# Sp_pico.net
KiCad netlist of a schematic drawn in EAGLE
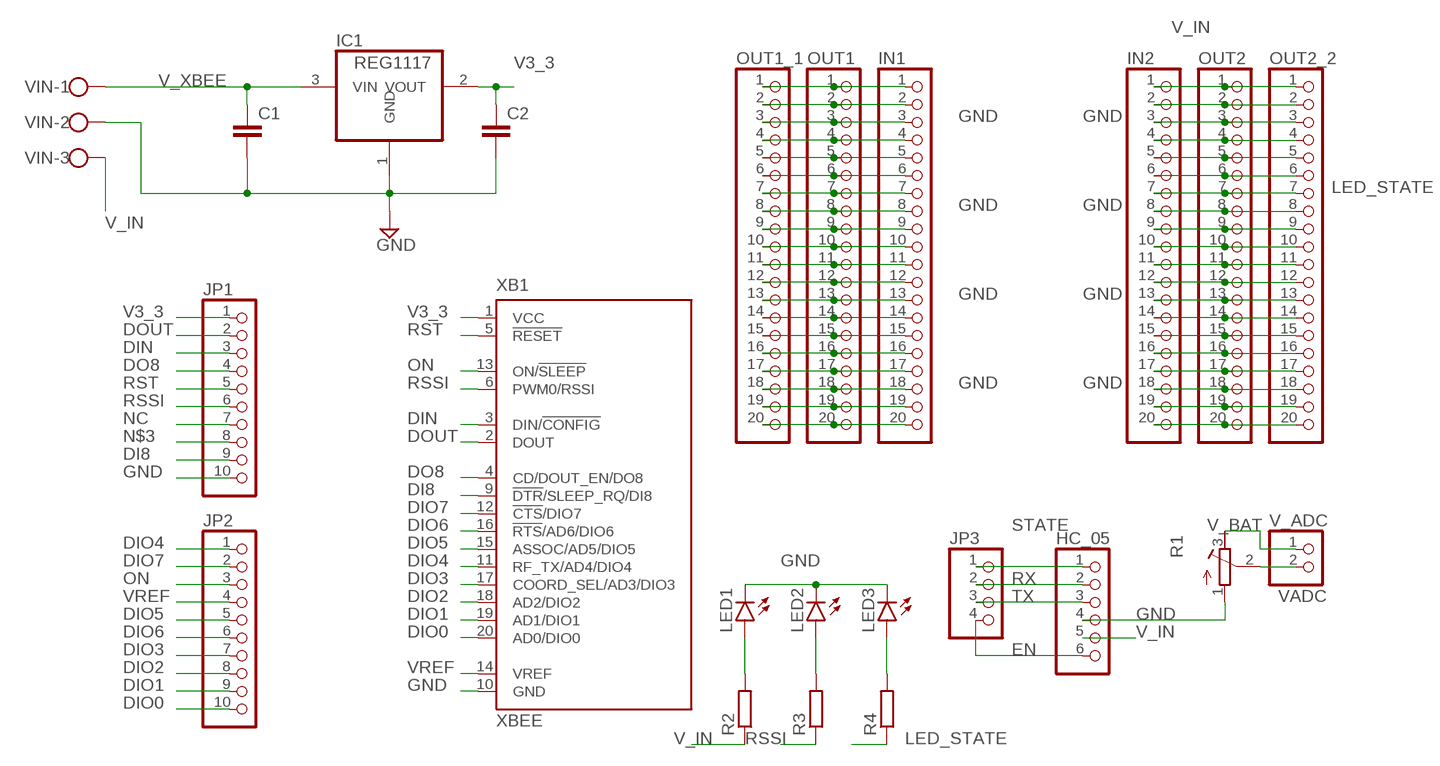
[diagram p0: schematic, sheet 1]

(export (version "E")
  (design (tool "Eeschema 10.0.6"))
  (components
    (comp (ref "C1")
      (value "C2.5/5")
      (footprint "eagle-import:C2.5-5")
      (libsource (lib "eagle-import") (part "C2.5/5"))
    )
    (comp (ref "C2")
      (value "C2.5/5")
      (footprint "eagle-import:C2.5-5")
      (libsource (lib "eagle-import") (part "C2.5/5"))
    )
    (comp (ref "HC_05")
      (value "PINHD-1X6")
      (footprint "eagle-import:1X06")
      (libsource (lib "eagle-import") (part "PINHD-1X6"))
    )
    (comp (ref "IC1")
      (value "REG1117")
      (footprint "eagle-import:SOT223")
      (libsource (lib "eagle-import") (part "REG1117"))
    )
    (comp (ref "IN1")
      (value "PINHD-1X20")
      (footprint "eagle-import:1X20")
      (libsource (lib "eagle-import") (part "PINHD-1X20"))
    )
    (comp (ref "IN2")
      (value "PINHD-1X20")
      (footprint "eagle-import:1X20")
      (libsource (lib "eagle-import") (part "PINHD-1X20"))
    )
    (comp (ref "JP1")
      (value "PINHD-1X10")
      (footprint "eagle-import:1X10")
      (libsource (lib "eagle-import") (part "PINHD-1X10"))
    )
    (comp (ref "JP2")
      (value "PINHD-1X10")
      (footprint "eagle-import:1X10")
      (libsource (lib "eagle-import") (part "PINHD-1X10"))
    )
    (comp (ref "JP3")
      (value "PINHD-1X4")
      (footprint "eagle-import:1X04")
      (libsource (lib "eagle-import") (part "PINHD-1X4"))
    )
    (comp (ref "LED1")
      (value "LED5MM")
      (footprint "eagle-import:LED5MM")
      (libsource (lib "eagle-import") (part "LED5MM"))
    )
    (comp (ref "LED2")
      (value "LED5MM")
      (footprint "eagle-import:LED5MM")
      (libsource (lib "eagle-import") (part "LED5MM"))
    )
    (comp (ref "LED3")
      (value "LED5MM")
      (footprint "eagle-import:LED5MM")
      (libsource (lib "eagle-import") (part "LED5MM"))
    )
    (comp (ref "OUT1")
      (value "PINHD-1X20")
      (footprint "eagle-import:1X20")
      (libsource (lib "eagle-import") (part "PINHD-1X20"))
    )
    (comp (ref "OUT1_1")
      (value "PINHD-1X20")
      (footprint "eagle-import:1X20")
      (libsource (lib "eagle-import") (part "PINHD-1X20"))
    )
    (comp (ref "OUT2")
      (value "PINHD-1X20")
      (footprint "eagle-import:1X20")
      (libsource (lib "eagle-import") (part "PINHD-1X20"))
    )
    (comp (ref "OUT2_2")
      (value "PINHD-1X20")
      (footprint "eagle-import:1X20")
      (libsource (lib "eagle-import") (part "PINHD-1X20"))
    )
    (comp (ref "R1")
      (value "R-TRIMM3296X")
      (footprint "eagle-import:RTRIM3296X")
      (libsource (lib "eagle-import") (part "R-TRIMM3296X"))
    )
    (comp (ref "R2")
      (value "R-EU_0204/7")
      (footprint "eagle-import:0204_7")
      (libsource (lib "eagle-import") (part "R-EU_0204/7"))
    )
    (comp (ref "R3")
      (value "R-EU_0204/7")
      (footprint "eagle-import:0204_7")
      (libsource (lib "eagle-import") (part "R-EU_0204/7"))
    )
    (comp (ref "R4")
      (value "R-EU_0204/7")
      (footprint "eagle-import:0204_7")
      (libsource (lib "eagle-import") (part "R-EU_0204/7"))
    )
    (comp (ref "VIN")
      (value "W237-103")
      (footprint "eagle-import:W237-103")
      (fields (field (name "MPN") "237-103"))
      (libsource (lib "eagle-import") (part "W237-103"))
    )
    (comp (ref "V_ADC")
      (value "PINHD-1X2")
      (footprint "eagle-import:1X02")
      (libsource (lib "eagle-import") (part "PINHD-1X2"))
    )
    (comp (ref "XB1")
      (value "XBEE")
      (footprint "eagle-import:XBEE")
      (fields (field (name "MPN") "XBP24-Z7UIT-004"))
      (libsource (lib "eagle-import") (part "XBEE"))
    )
  )
  (nets
    (net (code "1") (name "/DI8") (class "Default")
      (node (ref "JP1") (pin "9") (pinfunction "9_9") (pintype "passive"))
      (node (ref "XB1") (pin "9") (pinfunction "~{DTR}/SLEEP_RQ/DI8_9") (pintype "bidirectional"))
    )
    (net (code "2") (name "/DIN") (class "Default")
      (node (ref "JP1") (pin "3") (pinfunction "3_3") (pintype "passive"))
      (node (ref "XB1") (pin "3") (pinfunction "DIN/~{CONFIG}_3") (pintype "input"))
    )
    (net (code "3") (name "/DIO0") (class "Default")
      (node (ref "JP2") (pin "10") (pinfunction "10_10") (pintype "passive"))
      (node (ref "XB1") (pin "20") (pinfunction "AD0/DIO0_20") (pintype "bidirectional"))
    )
    (net (code "4") (name "/DIO1") (class "Default")
      (node (ref "JP2") (pin "9") (pinfunction "9_9") (pintype "passive"))
      (node (ref "XB1") (pin "19") (pinfunction "AD1/DIO1_19") (pintype "bidirectional"))
    )
    (net (code "5") (name "/DIO2") (class "Default")
      (node (ref "JP2") (pin "8") (pinfunction "8_8") (pintype "passive"))
      (node (ref "XB1") (pin "18") (pinfunction "AD2/DIO2_18") (pintype "bidirectional"))
    )
    (net (code "6") (name "/DIO3") (class "Default")
      (node (ref "JP2") (pin "7") (pinfunction "7_7") (pintype "passive"))
      (node (ref "XB1") (pin "17") (pinfunction "COORD_SEL/AD3/DIO3_17") (pintype "bidirectional"))
    )
    (net (code "7") (name "/DIO4") (class "Default")
      (node (ref "JP2") (pin "1") (pinfunction "1_1") (pintype "passive"))
      (node (ref "XB1") (pin "11") (pinfunction "RF_TX/AD4/DIO4_11") (pintype "bidirectional"))
    )
    (net (code "8") (name "/DIO5") (class "Default")
      (node (ref "JP2") (pin "5") (pinfunction "5_5") (pintype "passive"))
      (node (ref "XB1") (pin "15") (pinfunction "ASSOC/AD5/DIO5_15") (pintype "bidirectional"))
    )
    (net (code "9") (name "/DIO6") (class "Default")
      (node (ref "JP2") (pin "6") (pinfunction "6_6") (pintype "passive"))
      (node (ref "XB1") (pin "16") (pinfunction "~{RTS}/AD6/DIO6_16") (pintype "bidirectional"))
    )
    (net (code "10") (name "/DIO7") (class "Default")
      (node (ref "JP2") (pin "2") (pinfunction "2_2") (pintype "passive"))
      (node (ref "XB1") (pin "12") (pinfunction "~{CTS}/DIO7_12") (pintype "bidirectional"))
    )
    (net (code "11") (name "/DO8") (class "Default")
      (node (ref "JP1") (pin "4") (pinfunction "4_4") (pintype "passive"))
      (node (ref "XB1") (pin "4") (pinfunction "CD/DOUT_EN/DO8_4") (pintype "output"))
    )
    (net (code "12") (name "/DOUT") (class "Default")
      (node (ref "JP1") (pin "2") (pinfunction "2_2") (pintype "passive"))
      (node (ref "XB1") (pin "2") (pinfunction "DOUT_2") (pintype "output"))
    )
    (net (code "13") (name "/EN") (class "Default")
      (node (ref "HC_05") (pin "6") (pinfunction "6_6") (pintype "passive"))
      (node (ref "JP3") (pin "4") (pinfunction "4_4") (pintype "passive"))
    )
    (net (code "14") (name "/LED_STATE") (class "Default")
      (node (ref "IN2") (pin "7") (pinfunction "7_7") (pintype "passive"))
      (node (ref "OUT2") (pin "7") (pinfunction "7_7") (pintype "passive"))
      (node (ref "OUT2_2") (pin "7") (pinfunction "7_7") (pintype "passive"))
      (node (ref "R4") (pin "1") (pinfunction "1_1") (pintype "passive"))
    )
    (net (code "15") (name "/N$3") (class "Default")
      (node (ref "JP1") (pin "8") (pinfunction "8_8") (pintype "passive"))
    )
    (net (code "16") (name "/NC") (class "Default")
      (node (ref "JP1") (pin "7") (pinfunction "7_7") (pintype "passive"))
    )
    (net (code "17") (name "/ON") (class "Default")
      (node (ref "JP2") (pin "3") (pinfunction "3_3") (pintype "passive"))
      (node (ref "XB1") (pin "13") (pinfunction "ON/~{SLEEP}_13") (pintype "output"))
    )
    (net (code "18") (name "/RSSI") (class "Default")
      (node (ref "JP1") (pin "6") (pinfunction "6_6") (pintype "passive"))
      (node (ref "R3") (pin "1") (pinfunction "1_1") (pintype "passive"))
      (node (ref "XB1") (pin "6") (pinfunction "PWM0/RSSI_6") (pintype "output"))
    )
    (net (code "19") (name "/RST") (class "Default")
      (node (ref "JP1") (pin "5") (pinfunction "5_5") (pintype "passive"))
      (node (ref "XB1") (pin "5") (pinfunction "~{RESET}_5") (pintype "input"))
    )
    (net (code "20") (name "/RX") (class "Default")
      (node (ref "HC_05") (pin "2") (pinfunction "2_2") (pintype "passive"))
      (node (ref "JP3") (pin "2") (pinfunction "2_2") (pintype "passive"))
    )
    (net (code "21") (name "/STATE") (class "Default")
      (node (ref "HC_05") (pin "1") (pinfunction "1_1") (pintype "passive"))
      (node (ref "JP3") (pin "1") (pinfunction "1_1") (pintype "passive"))
    )
    (net (code "22") (name "/TX") (class "Default")
      (node (ref "HC_05") (pin "3") (pinfunction "3_3") (pintype "passive"))
      (node (ref "JP3") (pin "3") (pinfunction "3_3") (pintype "passive"))
    )
    (net (code "23") (name "/V3_3") (class "Default")
      (node (ref "C2") (pin "1") (pinfunction "1_1") (pintype "passive"))
      (node (ref "IC1") (pin "2") (pinfunction "VOUT_2") (pintype "output"))
      (node (ref "JP1") (pin "1") (pinfunction "1_1") (pintype "passive"))
      (node (ref "XB1") (pin "1") (pinfunction "VCC_1") (pintype "power_in"))
    )
    (net (code "24") (name "/VADC") (class "Default")
      (node (ref "R1") (pin "2") (pinfunction "S_2") (pintype "passive"))
      (node (ref "V_ADC") (pin "2") (pinfunction "2_2") (pintype "passive"))
    )
    (net (code "25") (name "/VREF") (class "Default")
      (node (ref "JP2") (pin "4") (pinfunction "4_4") (pintype "passive"))
      (node (ref "XB1") (pin "14") (pinfunction "VREF_14") (pintype "input"))
    )
    (net (code "26") (name "/V_BAT") (class "Default")
      (node (ref "R1") (pin "3") (pinfunction "E_3") (pintype "passive"))
      (node (ref "V_ADC") (pin "1") (pinfunction "1_1") (pintype "passive"))
    )
    (net (code "27") (name "/V_IN") (class "Default")
      (node (ref "HC_05") (pin "5") (pinfunction "5_5") (pintype "passive"))
      (node (ref "IN2") (pin "1") (pinfunction "1_1") (pintype "passive"))
      (node (ref "OUT2") (pin "1") (pinfunction "1_1") (pintype "passive"))
      (node (ref "OUT2_2") (pin "1") (pinfunction "1_1") (pintype "passive"))
      (node (ref "R2") (pin "1") (pinfunction "1_1") (pintype "passive"))
      (node (ref "VIN") (pin "3") (pinfunction "KL_3") (pintype "passive"))
    )
    (net (code "28") (name "/V_XBEE") (class "Default")
      (node (ref "C1") (pin "1") (pinfunction "1_1") (pintype "passive"))
      (node (ref "IC1") (pin "3") (pinfunction "VIN_3") (pintype "input"))
      (node (ref "VIN") (pin "1") (pinfunction "KL_1") (pintype "passive"))
    )
    (net (code "29") (name "GND") (class "Default")
      (node (ref "C1") (pin "2") (pinfunction "2_2") (pintype "passive"))
      (node (ref "C2") (pin "2") (pinfunction "2_2") (pintype "passive"))
      (node (ref "HC_05") (pin "4") (pinfunction "4_4") (pintype "passive"))
      (node (ref "IC1") (pin "1") (pinfunction "GND_1") (pintype "power_in"))
      (node (ref "IN1") (pin "13") (pinfunction "13_13") (pintype "passive"))
      (node (ref "IN1") (pin "18") (pinfunction "18_18") (pintype "passive"))
      (node (ref "IN1") (pin "3") (pinfunction "3_3") (pintype "passive"))
      (node (ref "IN1") (pin "8") (pinfunction "8_8") (pintype "passive"))
      (node (ref "IN2") (pin "13") (pinfunction "13_13") (pintype "passive"))
      (node (ref "IN2") (pin "18") (pinfunction "18_18") (pintype "passive"))
      (node (ref "IN2") (pin "3") (pinfunction "3_3") (pintype "passive"))
      (node (ref "IN2") (pin "8") (pinfunction "8_8") (pintype "passive"))
      (node (ref "JP1") (pin "10") (pinfunction "10_10") (pintype "passive"))
      (node (ref "LED1") (pin "K") (pinfunction "C_K") (pintype "passive"))
      (node (ref "LED2") (pin "K") (pinfunction "C_K") (pintype "passive"))
      (node (ref "LED3") (pin "K") (pinfunction "C_K") (pintype "passive"))
      (node (ref "OUT1") (pin "13") (pinfunction "13_13") (pintype "passive"))
      (node (ref "OUT1") (pin "18") (pinfunction "18_18") (pintype "passive"))
      (node (ref "OUT1") (pin "3") (pinfunction "3_3") (pintype "passive"))
      (node (ref "OUT1") (pin "8") (pinfunction "8_8") (pintype "passive"))
      (node (ref "OUT1_1") (pin "13") (pinfunction "13_13") (pintype "passive"))
      (node (ref "OUT1_1") (pin "18") (pinfunction "18_18") (pintype "passive"))
      (node (ref "OUT1_1") (pin "3") (pinfunction "3_3") (pintype "passive"))
      (node (ref "OUT1_1") (pin "8") (pinfunction "8_8") (pintype "passive"))
      (node (ref "OUT2") (pin "13") (pinfunction "13_13") (pintype "passive"))
      (node (ref "OUT2") (pin "18") (pinfunction "18_18") (pintype "passive"))
      (node (ref "OUT2") (pin "3") (pinfunction "3_3") (pintype "passive"))
      (node (ref "OUT2") (pin "8") (pinfunction "8_8") (pintype "passive"))
      (node (ref "OUT2_2") (pin "13") (pinfunction "13_13") (pintype "passive"))
      (node (ref "OUT2_2") (pin "18") (pinfunction "18_18") (pintype "passive"))
      (node (ref "OUT2_2") (pin "3") (pinfunction "3_3") (pintype "passive"))
      (node (ref "OUT2_2") (pin "8") (pinfunction "8_8") (pintype "passive"))
      (node (ref "R1") (pin "1") (pinfunction "A_1") (pintype "passive"))
      (node (ref "VIN") (pin "2") (pinfunction "KL_2") (pintype "passive"))
      (node (ref "XB1") (pin "10") (pinfunction "GND_10") (pintype "power_in"))
    )
    (net (code "30") (name "Net-(IN1-Pad1)") (class "Default")
      (node (ref "IN1") (pin "1") (pinfunction "1_1") (pintype "passive"))
      (node (ref "OUT1") (pin "1") (pinfunction "1_1") (pintype "passive"))
      (node (ref "OUT1_1") (pin "1") (pinfunction "1_1") (pintype "passive"))
    )
    (net (code "31") (name "Net-(IN1-Pad2)") (class "Default")
      (node (ref "IN1") (pin "2") (pinfunction "2_2") (pintype "passive"))
      (node (ref "OUT1") (pin "2") (pinfunction "2_2") (pintype "passive"))
      (node (ref "OUT1_1") (pin "2") (pinfunction "2_2") (pintype "passive"))
    )
    (net (code "32") (name "Net-(IN1-Pad4)") (class "Default")
      (node (ref "IN1") (pin "4") (pinfunction "4_4") (pintype "passive"))
      (node (ref "OUT1") (pin "4") (pinfunction "4_4") (pintype "passive"))
      (node (ref "OUT1_1") (pin "4") (pinfunction "4_4") (pintype "passive"))
    )
    (net (code "33") (name "Net-(IN1-Pad5)") (class "Default")
      (node (ref "IN1") (pin "5") (pinfunction "5_5") (pintype "passive"))
      (node (ref "OUT1") (pin "5") (pinfunction "5_5") (pintype "passive"))
      (node (ref "OUT1_1") (pin "5") (pinfunction "5_5") (pintype "passive"))
    )
    (net (code "34") (name "Net-(IN1-Pad6)") (class "Default")
      (node (ref "IN1") (pin "6") (pinfunction "6_6") (pintype "passive"))
      (node (ref "OUT1") (pin "6") (pinfunction "6_6") (pintype "passive"))
      (node (ref "OUT1_1") (pin "6") (pinfunction "6_6") (pintype "passive"))
    )
    (net (code "35") (name "Net-(IN1-Pad7)") (class "Default")
      (node (ref "IN1") (pin "7") (pinfunction "7_7") (pintype "passive"))
      (node (ref "OUT1") (pin "7") (pinfunction "7_7") (pintype "passive"))
      (node (ref "OUT1_1") (pin "7") (pinfunction "7_7") (pintype "passive"))
    )
    (net (code "36") (name "Net-(IN1-Pad9)") (class "Default")
      (node (ref "IN1") (pin "9") (pinfunction "9_9") (pintype "passive"))
      (node (ref "OUT1") (pin "9") (pinfunction "9_9") (pintype "passive"))
      (node (ref "OUT1_1") (pin "9") (pinfunction "9_9") (pintype "passive"))
    )
    (net (code "37") (name "Net-(IN1-Pad10)") (class "Default")
      (node (ref "IN1") (pin "10") (pinfunction "10_10") (pintype "passive"))
      (node (ref "OUT1") (pin "10") (pinfunction "10_10") (pintype "passive"))
      (node (ref "OUT1_1") (pin "10") (pinfunction "10_10") (pintype "passive"))
    )
    (net (code "38") (name "Net-(IN1-Pad11)") (class "Default")
      (node (ref "IN1") (pin "11") (pinfunction "11_11") (pintype "passive"))
      (node (ref "OUT1") (pin "11") (pinfunction "11_11") (pintype "passive"))
      (node (ref "OUT1_1") (pin "11") (pinfunction "11_11") (pintype "passive"))
    )
    (net (code "39") (name "Net-(IN1-Pad12)") (class "Default")
      (node (ref "IN1") (pin "12") (pinfunction "12_12") (pintype "passive"))
      (node (ref "OUT1") (pin "12") (pinfunction "12_12") (pintype "passive"))
      (node (ref "OUT1_1") (pin "12") (pinfunction "12_12") (pintype "passive"))
    )
    (net (code "40") (name "Net-(IN1-Pad14)") (class "Default")
      (node (ref "IN1") (pin "14") (pinfunction "14_14") (pintype "passive"))
      (node (ref "OUT1") (pin "14") (pinfunction "14_14") (pintype "passive"))
      (node (ref "OUT1_1") (pin "14") (pinfunction "14_14") (pintype "passive"))
    )
    (net (code "41") (name "Net-(IN1-Pad15)") (class "Default")
      (node (ref "IN1") (pin "15") (pinfunction "15_15") (pintype "passive"))
      (node (ref "OUT1") (pin "15") (pinfunction "15_15") (pintype "passive"))
      (node (ref "OUT1_1") (pin "15") (pinfunction "15_15") (pintype "passive"))
    )
    (net (code "42") (name "Net-(IN1-Pad16)") (class "Default")
      (node (ref "IN1") (pin "16") (pinfunction "16_16") (pintype "passive"))
      (node (ref "OUT1") (pin "16") (pinfunction "16_16") (pintype "passive"))
      (node (ref "OUT1_1") (pin "16") (pinfunction "16_16") (pintype "passive"))
    )
    (net (code "43") (name "Net-(IN1-Pad17)") (class "Default")
      (node (ref "IN1") (pin "17") (pinfunction "17_17") (pintype "passive"))
      (node (ref "OUT1") (pin "17") (pinfunction "17_17") (pintype "passive"))
      (node (ref "OUT1_1") (pin "17") (pinfunction "17_17") (pintype "passive"))
    )
    (net (code "44") (name "Net-(IN1-Pad19)") (class "Default")
      (node (ref "IN1") (pin "19") (pinfunction "19_19") (pintype "passive"))
      (node (ref "OUT1") (pin "19") (pinfunction "19_19") (pintype "passive"))
      (node (ref "OUT1_1") (pin "19") (pinfunction "19_19") (pintype "passive"))
    )
    (net (code "45") (name "Net-(IN1-Pad20)") (class "Default")
      (node (ref "IN1") (pin "20") (pinfunction "20_20") (pintype "passive"))
      (node (ref "OUT1") (pin "20") (pinfunction "20_20") (pintype "passive"))
      (node (ref "OUT1_1") (pin "20") (pinfunction "20_20") (pintype "passive"))
    )
    (net (code "46") (name "Net-(IN2-Pad2)") (class "Default")
      (node (ref "IN2") (pin "2") (pinfunction "2_2") (pintype "passive"))
      (node (ref "OUT2") (pin "2") (pinfunction "2_2") (pintype "passive"))
      (node (ref "OUT2_2") (pin "2") (pinfunction "2_2") (pintype "passive"))
    )
    (net (code "47") (name "Net-(IN2-Pad4)") (class "Default")
      (node (ref "IN2") (pin "4") (pinfunction "4_4") (pintype "passive"))
      (node (ref "OUT2") (pin "4") (pinfunction "4_4") (pintype "passive"))
      (node (ref "OUT2_2") (pin "4") (pinfunction "4_4") (pintype "passive"))
    )
    (net (code "48") (name "Net-(IN2-Pad5)") (class "Default")
      (node (ref "IN2") (pin "5") (pinfunction "5_5") (pintype "passive"))
      (node (ref "OUT2") (pin "5") (pinfunction "5_5") (pintype "passive"))
      (node (ref "OUT2_2") (pin "5") (pinfunction "5_5") (pintype "passive"))
    )
    (net (code "49") (name "Net-(IN2-Pad6)") (class "Default")
      (node (ref "IN2") (pin "6") (pinfunction "6_6") (pintype "passive"))
      (node (ref "OUT2") (pin "6") (pinfunction "6_6") (pintype "passive"))
      (node (ref "OUT2_2") (pin "6") (pinfunction "6_6") (pintype "passive"))
    )
    (net (code "50") (name "Net-(IN2-Pad9)") (class "Default")
      (node (ref "IN2") (pin "9") (pinfunction "9_9") (pintype "passive"))
      (node (ref "OUT2") (pin "9") (pinfunction "9_9") (pintype "passive"))
      (node (ref "OUT2_2") (pin "9") (pinfunction "9_9") (pintype "passive"))
    )
    (net (code "51") (name "Net-(IN2-Pad10)") (class "Default")
      (node (ref "IN2") (pin "10") (pinfunction "10_10") (pintype "passive"))
      (node (ref "OUT2") (pin "10") (pinfunction "10_10") (pintype "passive"))
      (node (ref "OUT2_2") (pin "10") (pinfunction "10_10") (pintype "passive"))
    )
    (net (code "52") (name "Net-(IN2-Pad11)") (class "Default")
      (node (ref "IN2") (pin "11") (pinfunction "11_11") (pintype "passive"))
      (node (ref "OUT2") (pin "11") (pinfunction "11_11") (pintype "passive"))
      (node (ref "OUT2_2") (pin "11") (pinfunction "11_11") (pintype "passive"))
    )
    (net (code "53") (name "Net-(IN2-Pad12)") (class "Default")
      (node (ref "IN2") (pin "12") (pinfunction "12_12") (pintype "passive"))
      (node (ref "OUT2") (pin "12") (pinfunction "12_12") (pintype "passive"))
      (node (ref "OUT2_2") (pin "12") (pinfunction "12_12") (pintype "passive"))
    )
    (net (code "54") (name "Net-(IN2-Pad14)") (class "Default")
      (node (ref "IN2") (pin "14") (pinfunction "14_14") (pintype "passive"))
      (node (ref "OUT2") (pin "14") (pinfunction "14_14") (pintype "passive"))
      (node (ref "OUT2_2") (pin "14") (pinfunction "14_14") (pintype "passive"))
    )
    (net (code "55") (name "Net-(IN2-Pad15)") (class "Default")
      (node (ref "IN2") (pin "15") (pinfunction "15_15") (pintype "passive"))
      (node (ref "OUT2") (pin "15") (pinfunction "15_15") (pintype "passive"))
      (node (ref "OUT2_2") (pin "15") (pinfunction "15_15") (pintype "passive"))
    )
    (net (code "56") (name "Net-(IN2-Pad16)") (class "Default")
      (node (ref "IN2") (pin "16") (pinfunction "16_16") (pintype "passive"))
      (node (ref "OUT2") (pin "16") (pinfunction "16_16") (pintype "passive"))
      (node (ref "OUT2_2") (pin "16") (pinfunction "16_16") (pintype "passive"))
    )
    (net (code "57") (name "Net-(IN2-Pad17)") (class "Default")
      (node (ref "IN2") (pin "17") (pinfunction "17_17") (pintype "passive"))
      (node (ref "OUT2") (pin "17") (pinfunction "17_17") (pintype "passive"))
      (node (ref "OUT2_2") (pin "17") (pinfunction "17_17") (pintype "passive"))
    )
    (net (code "58") (name "Net-(IN2-Pad19)") (class "Default")
      (node (ref "IN2") (pin "19") (pinfunction "19_19") (pintype "passive"))
      (node (ref "OUT2") (pin "19") (pinfunction "19_19") (pintype "passive"))
      (node (ref "OUT2_2") (pin "19") (pinfunction "19_19") (pintype "passive"))
    )
    (net (code "59") (name "Net-(IN2-Pad20)") (class "Default")
      (node (ref "IN2") (pin "20") (pinfunction "20_20") (pintype "passive"))
      (node (ref "OUT2") (pin "20") (pinfunction "20_20") (pintype "passive"))
      (node (ref "OUT2_2") (pin "20") (pinfunction "20_20") (pintype "passive"))
    )
    (net (code "60") (name "Net-(LED1-PadA)") (class "Default")
      (node (ref "LED1") (pin "A") (pinfunction "A_A") (pintype "passive"))
      (node (ref "R2") (pin "2") (pinfunction "2_2") (pintype "passive"))
    )
    (net (code "61") (name "Net-(LED2-PadA)") (class "Default")
      (node (ref "LED2") (pin "A") (pinfunction "A_A") (pintype "passive"))
      (node (ref "R3") (pin "2") (pinfunction "2_2") (pintype "passive"))
    )
    (net (code "62") (name "Net-(LED3-PadA)") (class "Default")
      (node (ref "LED3") (pin "A") (pinfunction "A_A") (pintype "passive"))
      (node (ref "R4") (pin "2") (pinfunction "2_2") (pintype "passive"))
    )
  )
)
